# PowerSupply.net
KiCad netlist of a schematic drawn in Altium Designer
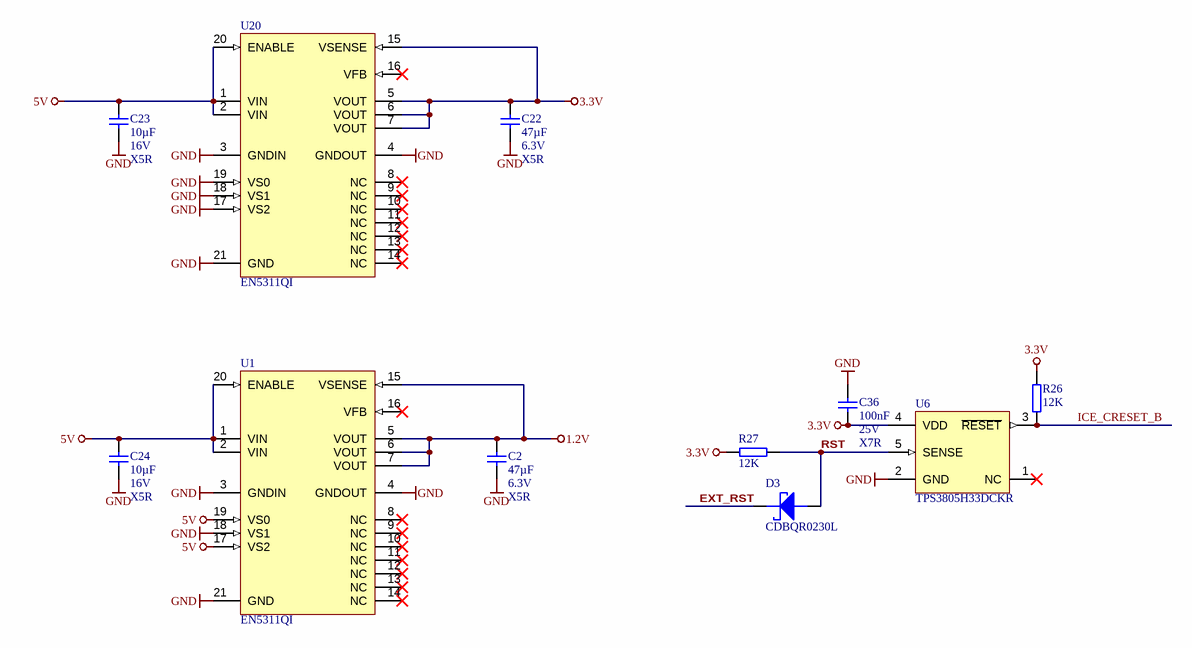
[diagram p0: PowerSupply.SchDoc]

(export (version "E")
  (design (tool "Eeschema 10.0.6"))
  (components
    (comp (ref "C2")
      (value "47µF")
      (footprint "CAPC2012X135N")
      (description "KON 47µF 6,3V  X5R SMD 20%")
      (fields
        (field (name "VOLTAGE") "6.3V")
        (field (name "TECHNOLOGY") "X5R")
        (field (name "TOLERANCE") "20%")
      )
      (libsource (lib "TE") (part "CAP-NP"))
    )
    (comp (ref "C22")
      (value "47µF")
      (footprint "CAPC2012X135N")
      (description "KON 47µF 6,3V  X5R SMD 20%")
      (fields
        (field (name "VOLTAGE") "6.3V")
        (field (name "TECHNOLOGY") "X5R")
        (field (name "TOLERANCE") "20%")
      )
      (libsource (lib "TE") (part "CAP-NP"))
    )
    (comp (ref "C23")
      (value "10µF")
      (footprint "CAPC1608X90N")
      (description "KON 10µF 16V X5R SMD 20%")
      (fields
        (field (name "VOLTAGE") "16V")
        (field (name "TECHNOLOGY") "X5R")
        (field (name "TOLERANCE") "20%")
      )
      (libsource (lib "TE") (part "CAP-NP"))
    )
    (comp (ref "C24")
      (value "10µF")
      (footprint "CAPC1608X90N")
      (description "KON 10µF 16V X5R SMD 20%")
      (fields
        (field (name "VOLTAGE") "16V")
        (field (name "TECHNOLOGY") "X5R")
        (field (name "TOLERANCE") "20%")
      )
      (libsource (lib "TE") (part "CAP-NP"))
    )
    (comp (ref "C36")
      (value "100nF")
      (footprint "CAPC1005X55N")
      (description "KON 100nF 25V X5R SMD")
      (fields (field (name "VOLTAGE") "25V") (field (name "TECHNOLOGY") "X7R"))
      (libsource (lib "TE") (part "CAP-NP"))
    )
    (comp (ref "D3")
      (value "CDBQR0230L")
      (footprint "DIOC1006X55N")
      (fields (field (name "VOLTAGE") "0.2A"))
      (libsource (lib "TE") (part "SCHOTTKY"))
    )
    (comp (ref "R26")
      (value "12K")
      (footprint "RESC1005X40N")
      (description "WID SMD 12K 1% 0,063W")
      (libsource (lib "TE") (part "RES"))
    )
    (comp (ref "R27")
      (value "12K")
      (footprint "RESC1005X40N")
      (description "WID SMD 12K 1% 0,063W")
      (libsource (lib "TE") (part "RES"))
    )
    (comp (ref "U1") (value "EN5311QI") (footprint "EN5311QI") (libsource (lib "TE") (part "EN5311QI")))
    (comp (ref "U6")
      (value "TPS3805H33DCKR")
      (footprint "SOT65P210X110-5N")
      (libsource (lib "TE") (part "TPS3805H33DCK"))
    )
    (comp (ref "U20") (value "EN5311QI") (footprint "EN5311QI") (libsource (lib "TE") (part "EN5311QI")))
  )
  (nets
    (net (code "1") (name "/EXT_RST") (class "Default")
      (node (ref "D3") (pin "1") (pinfunction "KATHODE_1") (pintype "passive"))
    )
    (net (code "2") (name "/ICE_CRESET_B") (class "Default")
      (node (ref "R26") (pin "1") (pinfunction "1_1") (pintype "passive"))
      (node (ref "U6") (pin "3") (pinfunction "~{RESET}_3") (pintype "output"))
    )
    (net (code "3") (name "/RST") (class "Default")
      (node (ref "D3") (pin "2") (pinfunction "ANODE_2") (pintype "passive"))
      (node (ref "R27") (pin "1") (pinfunction "1_1") (pintype "passive"))
      (node (ref "U6") (pin "5") (pinfunction "SENSE_5") (pintype "input"))
    )
    (net (code "4") (name "1.2V") (class "Default")
      (node (ref "C2") (pin "2") (pinfunction "2_2") (pintype "passive"))
      (node (ref "U1") (pin "15") (pinfunction "VSENSE_15") (pintype "input"))
      (node (ref "U1") (pin "5") (pinfunction "VOUT_5") (pintype "power_in"))
      (node (ref "U1") (pin "6") (pinfunction "VOUT_6") (pintype "power_in"))
      (node (ref "U1") (pin "7") (pinfunction "VOUT_7") (pintype "power_in"))
    )
    (net (code "5") (name "3.3V") (class "Default")
      (node (ref "C22") (pin "2") (pinfunction "2_2") (pintype "passive"))
      (node (ref "C36") (pin "2") (pinfunction "2_2") (pintype "passive"))
      (node (ref "R26") (pin "2") (pinfunction "2_2") (pintype "passive"))
      (node (ref "R27") (pin "2") (pinfunction "2_2") (pintype "passive"))
      (node (ref "U20") (pin "15") (pinfunction "VSENSE_15") (pintype "input"))
      (node (ref "U20") (pin "5") (pinfunction "VOUT_5") (pintype "power_in"))
      (node (ref "U20") (pin "6") (pinfunction "VOUT_6") (pintype "power_in"))
      (node (ref "U20") (pin "7") (pinfunction "VOUT_7") (pintype "power_in"))
      (node (ref "U6") (pin "4") (pinfunction "VDD_4") (pintype "power_in"))
    )
    (net (code "6") (name "5V") (class "Default")
      (node (ref "C23") (pin "1") (pinfunction "1_1") (pintype "passive"))
      (node (ref "C24") (pin "1") (pinfunction "1_1") (pintype "passive"))
      (node (ref "U1") (pin "1") (pinfunction "VIN_1") (pintype "power_in"))
      (node (ref "U1") (pin "17") (pinfunction "VS2_17") (pintype "input"))
      (node (ref "U1") (pin "19") (pinfunction "VS0_19") (pintype "input"))
      (node (ref "U1") (pin "2") (pinfunction "VIN_2") (pintype "power_in"))
      (node (ref "U1") (pin "20") (pinfunction "ENABLE_20") (pintype "input"))
      (node (ref "U20") (pin "1") (pinfunction "VIN_1") (pintype "power_in"))
      (node (ref "U20") (pin "2") (pinfunction "VIN_2") (pintype "power_in"))
      (node (ref "U20") (pin "20") (pinfunction "ENABLE_20") (pintype "input"))
    )
    (net (code "7") (name "GND") (class "Default")
      (node (ref "C2") (pin "1") (pinfunction "1_1") (pintype "passive"))
      (node (ref "C22") (pin "1") (pinfunction "1_1") (pintype "passive"))
      (node (ref "C23") (pin "2") (pinfunction "2_2") (pintype "passive"))
      (node (ref "C24") (pin "2") (pinfunction "2_2") (pintype "passive"))
      (node (ref "C36") (pin "1") (pinfunction "1_1") (pintype "passive"))
      (node (ref "U1") (pin "18") (pinfunction "VS1_18") (pintype "input"))
      (node (ref "U1") (pin "21") (pinfunction "GND_21") (pintype "power_in"))
      (node (ref "U1") (pin "3") (pinfunction "GNDIN_3") (pintype "power_in"))
      (node (ref "U1") (pin "4") (pinfunction "GNDOUT_4") (pintype "power_in"))
      (node (ref "U20") (pin "17") (pinfunction "VS2_17") (pintype "input"))
      (node (ref "U20") (pin "18") (pinfunction "VS1_18") (pintype "input"))
      (node (ref "U20") (pin "19") (pinfunction "VS0_19") (pintype "input"))
      (node (ref "U20") (pin "21") (pinfunction "GND_21") (pintype "power_in"))
      (node (ref "U20") (pin "3") (pinfunction "GNDIN_3") (pintype "power_in"))
      (node (ref "U20") (pin "4") (pinfunction "GNDOUT_4") (pintype "power_in"))
      (node (ref "U6") (pin "2") (pinfunction "GND_2") (pintype "power_in"))
    )
    (net (code "8") (name "unconnected-(U1-NC-Pad8)") (class "Default")
      (node (ref "U1") (pin "8") (pinfunction "NC_8") (pintype "passive+no_connect"))
    )
    (net (code "9") (name "unconnected-(U1-NC-Pad9)") (class "Default")
      (node (ref "U1") (pin "9") (pinfunction "NC_9") (pintype "passive+no_connect"))
    )
    (net (code "10") (name "unconnected-(U1-NC-Pad10)") (class "Default")
      (node (ref "U1") (pin "10") (pinfunction "NC_10") (pintype "passive+no_connect"))
    )
    (net (code "11") (name "unconnected-(U1-NC-Pad11)") (class "Default")
      (node (ref "U1") (pin "11") (pinfunction "NC_11") (pintype "passive+no_connect"))
    )
    (net (code "12") (name "unconnected-(U1-NC-Pad12)") (class "Default")
      (node (ref "U1") (pin "12") (pinfunction "NC_12") (pintype "passive+no_connect"))
    )
    (net (code "13") (name "unconnected-(U1-NC-Pad13)") (class "Default")
      (node (ref "U1") (pin "13") (pinfunction "NC_13") (pintype "passive+no_connect"))
    )
    (net (code "14") (name "unconnected-(U1-NC-Pad14)") (class "Default")
      (node (ref "U1") (pin "14") (pinfunction "NC_14") (pintype "passive+no_connect"))
    )
    (net (code "15") (name "unconnected-(U1-VFB-Pad16)") (class "Default")
      (node (ref "U1") (pin "16") (pinfunction "VFB_16") (pintype "input+no_connect"))
    )
    (net (code "16") (name "unconnected-(U6-NC-Pad1)") (class "Default")
      (node (ref "U6") (pin "1") (pinfunction "NC_1") (pintype "passive+no_connect"))
    )
    (net (code "17") (name "unconnected-(U20-NC-Pad8)") (class "Default")
      (node (ref "U20") (pin "8") (pinfunction "NC_8") (pintype "passive+no_connect"))
    )
    (net (code "18") (name "unconnected-(U20-NC-Pad9)") (class "Default")
      (node (ref "U20") (pin "9") (pinfunction "NC_9") (pintype "passive+no_connect"))
    )
    (net (code "19") (name "unconnected-(U20-NC-Pad10)") (class "Default")
      (node (ref "U20") (pin "10") (pinfunction "NC_10") (pintype "passive+no_connect"))
    )
    (net (code "20") (name "unconnected-(U20-NC-Pad11)") (class "Default")
      (node (ref "U20") (pin "11") (pinfunction "NC_11") (pintype "passive+no_connect"))
    )
    (net (code "21") (name "unconnected-(U20-NC-Pad12)") (class "Default")
      (node (ref "U20") (pin "12") (pinfunction "NC_12") (pintype "passive+no_connect"))
    )
    (net (code "22") (name "unconnected-(U20-NC-Pad13)") (class "Default")
      (node (ref "U20") (pin "13") (pinfunction "NC_13") (pintype "passive+no_connect"))
    )
    (net (code "23") (name "unconnected-(U20-NC-Pad14)") (class "Default")
      (node (ref "U20") (pin "14") (pinfunction "NC_14") (pintype "passive+no_connect"))
    )
    (net (code "24") (name "unconnected-(U20-VFB-Pad16)") (class "Default")
      (node (ref "U20") (pin "16") (pinfunction "VFB_16") (pintype "input+no_connect"))
    )
  )
)
